# LAN.net
KiCad netlist of a schematic drawn in Altium Designer
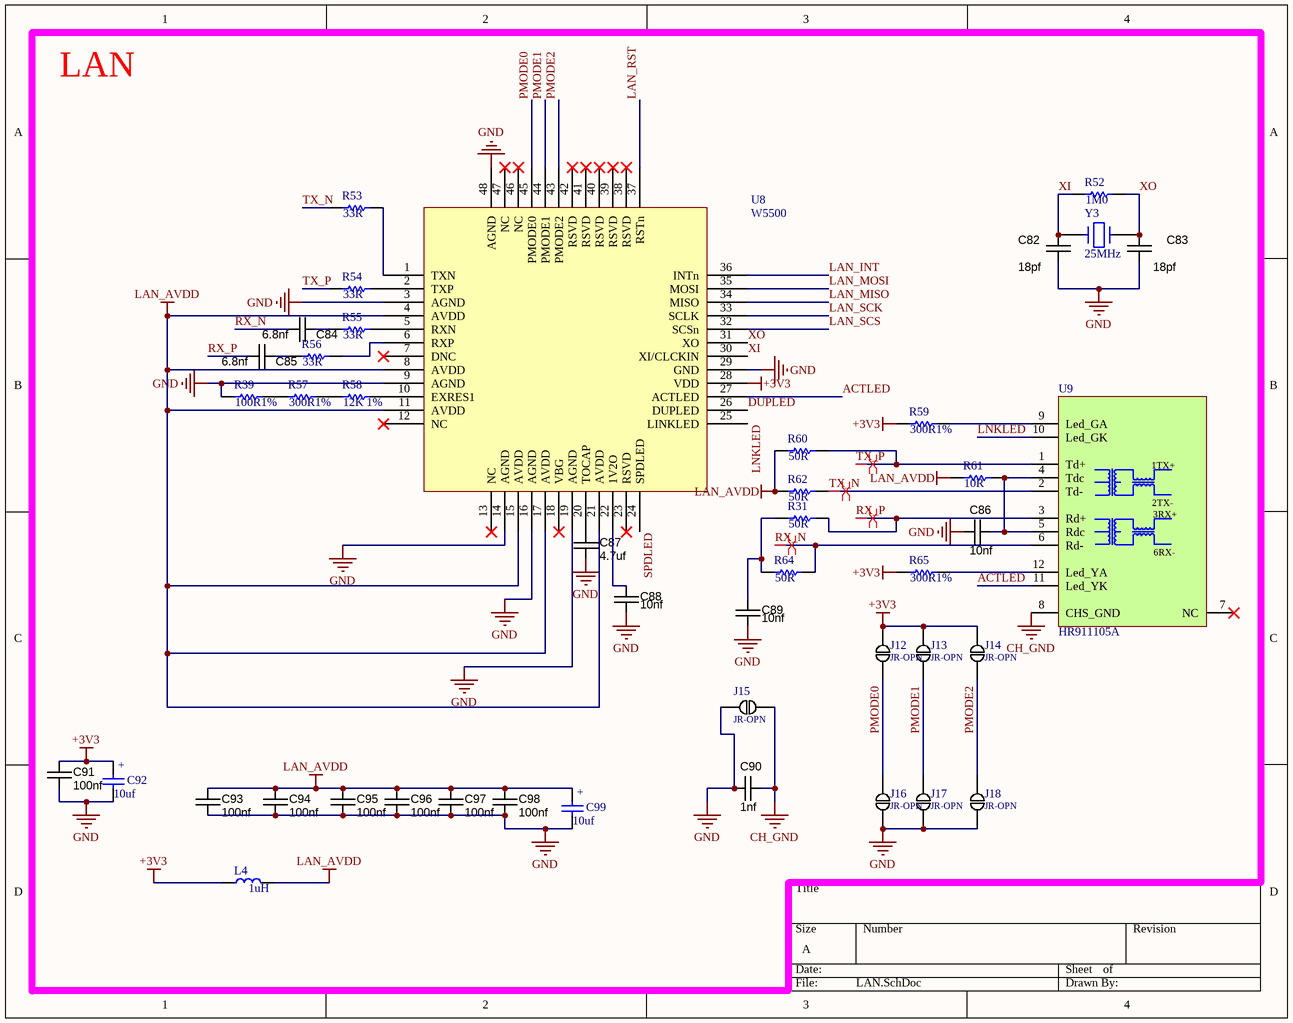
[diagram p0: LAN.SchDoc]

(export (version "E")
  (design (tool "Eeschema 10.0.6"))
  (components
    (comp (ref "C82")
      (value "18pf")
      (footprint "CAPC1608X90N")
      (description "Capacitor SMD Cer 100nF 10% 50V X7R 0603")
      (fields (field (name "TOLERANCE") "±10%"))
      (libsource (lib "altium-import") (part "root_2_CAPC_100n_0603_X7R_50V_10%_"))
    )
    (comp (ref "C83")
      (value "18pf")
      (footprint "CAPC1608X90N")
      (description "Capacitor SMD Cer 100nF 10% 50V X7R 0603")
      (fields (field (name "TOLERANCE") "±10%"))
      (libsource (lib "altium-import") (part "root_2_CAPC_100n_0603_X7R_50V_10%_"))
    )
    (comp (ref "C84")
      (value "6.8nf")
      (footprint "CAPC1608X90N")
      (description "Capacitor SMD Cer 100nF 10% 50V X7R 0603")
      (fields (field (name "TOLERANCE") "±10%"))
      (libsource (lib "altium-import") (part "root_3_CAPC_100n_0603_X7R_50V_10%_"))
    )
    (comp (ref "C85")
      (value "6.8nf")
      (footprint "CAPC1608X90N")
      (description "Capacitor SMD Cer 100nF 10% 50V X7R 0603")
      (fields (field (name "TOLERANCE") "±10%"))
      (libsource (lib "altium-import") (part "root_3_CAPC_100n_0603_X7R_50V_10%_"))
    )
    (comp (ref "C86")
      (value "10nf")
      (footprint "CAPC1608X90N")
      (description "Capacitor SMD Cer 100nF 10% 50V X7R 0603")
      (fields (field (name "TOLERANCE") "±10%"))
      (libsource (lib "altium-import") (part "root_1_CAPC_100n_0603_X7R_50V_10%_"))
    )
    (comp (ref "C87")
      (value "4.7uf")
      (footprint "CAPC1608X90N")
      (description "Capacitor SMD Cer 100nF 10% 50V X7R 0603")
      (fields (field (name "TOLERANCE") "±10%"))
      (libsource (lib "altium-import") (part "root_2_CAPC_100n_0603_X7R_50V_10%_"))
    )
    (comp (ref "C88")
      (value "10nf")
      (footprint "CAPC1608X90N")
      (description "Capacitor SMD Cer 100nF 10% 50V X7R 0603")
      (fields (field (name "TOLERANCE") "±10%"))
      (libsource (lib "altium-import") (part "root_2_CAPC_100n_0603_X7R_50V_10%_"))
    )
    (comp (ref "C89")
      (value "10nf")
      (footprint "CAPC1608X90N")
      (description "Capacitor SMD Cer 100nF 10% 50V X7R 0603")
      (fields (field (name "TOLERANCE") "±10%"))
      (libsource (lib "altium-import") (part "root_2_CAPC_100n_0603_X7R_50V_10%_"))
    )
    (comp (ref "C90")
      (value "1nf")
      (footprint "CAPC1608X90N")
      (description "Capacitor SMD Cer 100nF 10% 50V X7R 0603")
      (fields (field (name "TOLERANCE") "±10%"))
      (libsource (lib "altium-import") (part "root_1_CAPC_100n_0603_X7R_50V_10%_"))
    )
    (comp (ref "C91")
      (value "100nf")
      (footprint "CAPC1608X90N")
      (description "Capacitor SMD Cer 100nF 10% 50V X7R 0603")
      (fields (field (name "TOLERANCE") "±10%"))
      (libsource (lib "altium-import") (part "root_2_CAPC_100n_0603_X7R_50V_10%_"))
    )
    (comp (ref "C92")
      (value "10uf")
      (footprint "MY_CAP_SMD-A")
      (description "3.2X1.6MM")
      (libsource (lib "altium-import") (part "root_3_CAP_TANTAL_A_"))
    )
    (comp (ref "C93")
      (value "100nf")
      (footprint "CAPC1608X90N")
      (description "Capacitor SMD Cer 100nF 10% 50V X7R 0603")
      (fields (field (name "TOLERANCE") "±10%"))
      (libsource (lib "altium-import") (part "root_2_CAPC_100n_0603_X7R_50V_10%_"))
    )
    (comp (ref "C94")
      (value "100nf")
      (footprint "CAPC1608X90N")
      (description "Capacitor SMD Cer 100nF 10% 50V X7R 0603")
      (fields (field (name "TOLERANCE") "±10%"))
      (libsource (lib "altium-import") (part "root_2_CAPC_100n_0603_X7R_50V_10%_"))
    )
    (comp (ref "C95")
      (value "100nf")
      (footprint "CAPC1608X90N")
      (description "Capacitor SMD Cer 100nF 10% 50V X7R 0603")
      (fields (field (name "TOLERANCE") "±10%"))
      (libsource (lib "altium-import") (part "root_2_CAPC_100n_0603_X7R_50V_10%_"))
    )
    (comp (ref "C96")
      (value "100nf")
      (footprint "CAPC1608X90N")
      (description "Capacitor SMD Cer 100nF 10% 50V X7R 0603")
      (fields (field (name "TOLERANCE") "±10%"))
      (libsource (lib "altium-import") (part "root_2_CAPC_100n_0603_X7R_50V_10%_"))
    )
    (comp (ref "C97")
      (value "100nf")
      (footprint "CAPC1608X90N")
      (description "Capacitor SMD Cer 100nF 10% 50V X7R 0603")
      (fields (field (name "TOLERANCE") "±10%"))
      (libsource (lib "altium-import") (part "root_2_CAPC_100n_0603_X7R_50V_10%_"))
    )
    (comp (ref "C98")
      (value "100nf")
      (footprint "CAPC1608X90N")
      (description "Capacitor SMD Cer 100nF 10% 50V X7R 0603")
      (fields (field (name "TOLERANCE") "±10%"))
      (libsource (lib "altium-import") (part "root_2_CAPC_100n_0603_X7R_50V_10%_"))
    )
    (comp (ref "C99")
      (value "10uf")
      (footprint "MY_CAP_SMD-A")
      (description "3.2X1.6MM")
      (libsource (lib "altium-import") (part "root_3_CAP_TANTAL_A_"))
    )
    (comp (ref "J12")
      (value "JR-OPN")
      (footprint "0603-J")
      (description "SOLDERDOT BYPASS")
      (libsource (lib "*") (part "BYPASS"))
    )
    (comp (ref "J13")
      (value "JR-OPN")
      (footprint "0603-J")
      (description "SOLDERDOT BYPASS")
      (libsource (lib "*") (part "BYPASS"))
    )
    (comp (ref "J14")
      (value "JR-OPN")
      (footprint "0603-J")
      (description "SOLDERDOT BYPASS")
      (libsource (lib "*") (part "BYPASS"))
    )
    (comp (ref "J15")
      (value "JR-OPN")
      (footprint "0603-J")
      (description "SOLDERDOT BYPASS")
      (libsource (lib "*") (part "BYPASS"))
    )
    (comp (ref "J16")
      (value "JR-OPN")
      (footprint "0603-J")
      (description "SOLDERDOT BYPASS")
      (libsource (lib "*") (part "BYPASS"))
    )
    (comp (ref "J17")
      (value "JR-OPN")
      (footprint "0603-J")
      (description "SOLDERDOT BYPASS")
      (libsource (lib "*") (part "BYPASS"))
    )
    (comp (ref "J18")
      (value "JR-OPN")
      (footprint "0603-J")
      (description "SOLDERDOT BYPASS")
      (libsource (lib "*") (part "BYPASS"))
    )
    (comp (ref "L4")
      (value "1uH")
      (footprint "L0805")
      (description "Inductor SMD NC 0805")
      (libsource (lib "altium-import") (part "root_0_Inductor SMD NC 0805_"))
    )
    (comp (ref "R31")
      (value "50R")
      (footprint "Resistor_SMD_0603 (1608)")
      (description "Resistor 0603")
      (fields (field (name "PUBLISHER") "Seyed Razi Vesali") (field (name "EMAIL") "razi.vesali@gmail.com"))
      (libsource (lib "resistors") (part "Resistor"))
    )
    (comp (ref "R39")
      (value "100R1%")
      (footprint "Resistor_SMD_0603 (1608)")
      (description "Resistor 0603")
      (fields (field (name "PUBLISHER") "Seyed Razi Vesali") (field (name "EMAIL") "razi.vesali@gmail.com"))
      (libsource (lib "resistors") (part "Resistor"))
    )
    (comp (ref "R52")
      (value "1M0")
      (footprint "Resistor_SMD_0603 (1608)")
      (description "Resistor 0603")
      (fields (field (name "PUBLISHER") "Seyed Razi Vesali") (field (name "EMAIL") "razi.vesali@gmail.com"))
      (libsource (lib "resistors") (part "Resistor"))
    )
    (comp (ref "R53")
      (value "33R")
      (footprint "Resistor_SMD_0603 (1608)")
      (description "Resistor 0603")
      (fields (field (name "PUBLISHER") "Seyed Razi Vesali") (field (name "EMAIL") "razi.vesali@gmail.com"))
      (libsource (lib "resistors") (part "Resistor"))
    )
    (comp (ref "R54")
      (value "33R")
      (footprint "Resistor_SMD_0603 (1608)")
      (description "Resistor 0603")
      (fields (field (name "PUBLISHER") "Seyed Razi Vesali") (field (name "EMAIL") "razi.vesali@gmail.com"))
      (libsource (lib "resistors") (part "Resistor"))
    )
    (comp (ref "R55")
      (value "33R")
      (footprint "Resistor_SMD_0603 (1608)")
      (description "Resistor 0603")
      (fields (field (name "PUBLISHER") "Seyed Razi Vesali") (field (name "EMAIL") "razi.vesali@gmail.com"))
      (libsource (lib "resistors") (part "Resistor"))
    )
    (comp (ref "R56")
      (value "33R")
      (footprint "Resistor_SMD_0603 (1608)")
      (description "Resistor 0603")
      (fields (field (name "PUBLISHER") "Seyed Razi Vesali") (field (name "EMAIL") "razi.vesali@gmail.com"))
      (libsource (lib "resistors") (part "Resistor"))
    )
    (comp (ref "R57")
      (value "300R1%")
      (footprint "Resistor_SMD_0603 (1608)")
      (description "Resistor 0603")
      (fields (field (name "PUBLISHER") "Seyed Razi Vesali") (field (name "EMAIL") "razi.vesali@gmail.com"))
      (libsource (lib "resistors") (part "Resistor"))
    )
    (comp (ref "R58")
      (value "12K 1%")
      (footprint "Resistor_SMD_0603 (1608)")
      (description "Resistor 0603")
      (fields (field (name "PUBLISHER") "Seyed Razi Vesali") (field (name "EMAIL") "razi.vesali@gmail.com"))
      (libsource (lib "resistors") (part "Resistor"))
    )
    (comp (ref "R59")
      (value "300R1%")
      (footprint "Resistor_SMD_0603 (1608)")
      (description "Resistor 0603")
      (fields (field (name "PUBLISHER") "Seyed Razi Vesali") (field (name "EMAIL") "razi.vesali@gmail.com"))
      (libsource (lib "resistors") (part "Resistor"))
    )
    (comp (ref "R60")
      (value "50R")
      (footprint "Resistor_SMD_0603 (1608)")
      (description "Resistor 0603")
      (fields (field (name "PUBLISHER") "Seyed Razi Vesali") (field (name "EMAIL") "razi.vesali@gmail.com"))
      (libsource (lib "resistors") (part "Resistor"))
    )
    (comp (ref "R61")
      (value "10R")
      (footprint "Resistor_SMD_0603 (1608)")
      (description "Resistor 0603")
      (fields (field (name "PUBLISHER") "Seyed Razi Vesali") (field (name "EMAIL") "razi.vesali@gmail.com"))
      (libsource (lib "resistors") (part "Resistor"))
    )
    (comp (ref "R62")
      (value "50R")
      (footprint "Resistor_SMD_0603 (1608)")
      (description "Resistor 0603")
      (fields (field (name "PUBLISHER") "Seyed Razi Vesali") (field (name "EMAIL") "razi.vesali@gmail.com"))
      (libsource (lib "resistors") (part "Resistor"))
    )
    (comp (ref "R64")
      (value "50R")
      (footprint "Resistor_SMD_0603 (1608)")
      (description "Resistor 0603")
      (fields (field (name "PUBLISHER") "Seyed Razi Vesali") (field (name "EMAIL") "razi.vesali@gmail.com"))
      (libsource (lib "resistors") (part "Resistor"))
    )
    (comp (ref "R65")
      (value "300R1%")
      (footprint "Resistor_SMD_0603 (1608)")
      (description "Resistor 0603")
      (fields (field (name "PUBLISHER") "Seyed Razi Vesali") (field (name "EMAIL") "razi.vesali@gmail.com"))
      (libsource (lib "resistors") (part "Resistor"))
    )
    (comp (ref "U8")
      (value "W5500")
      (footprint "LQFP48")
      (description "Ethernet Controller, 10/100, SPI, DMA")
      (libsource (lib "altium-import") (part "root_0_W5500_"))
    )
    (comp (ref "U9")
      (value "HR911105A")
      (footprint "HR911105A")
      (description "RJ45, 10/100BASE, G/Y LED")
      (libsource (lib "altium-import") (part "root_0_HR911105A_"))
    )
    (comp (ref "Y3")
      (value "25MHz")
      (footprint "My_Crystal - SMD")
      (description "Crystal")
      (libsource (lib "altium-import") (part "root_0_CRYSTAL_SMD_"))
    )
  )
  (nets
    (net (code "1") (name "+3V3") (class "Default")
      (node (ref "C91") (pin "2") (pintype "passive"))
      (node (ref "C92") (pin "+") (pinfunction "+_+") (pintype "passive"))
      (node (ref "J12") (pin "1") (pinfunction "1_1") (pintype "passive"))
      (node (ref "J13") (pin "1") (pinfunction "1_1") (pintype "passive"))
      (node (ref "J14") (pin "1") (pinfunction "1_1") (pintype "passive"))
      (node (ref "L4") (pin "1") (pinfunction "1_1") (pintype "passive"))
      (node (ref "R59") (pin "1") (pinfunction "1_1") (pintype "passive"))
      (node (ref "R65") (pin "1") (pinfunction "1_1") (pintype "passive"))
      (node (ref "U8") (pin "28") (pinfunction "VDD_28") (pintype "passive"))
    )
    (net (code "2") (name "/ACTLED") (class "Default")
      (node (ref "U8") (pin "27") (pinfunction "ACTLED_27") (pintype "passive"))
      (node (ref "U9") (pin "11") (pinfunction "Led_YK_11") (pintype "passive"))
    )
    (net (code "3") (name "/DUPLED") (class "Default")
      (node (ref "U8") (pin "26") (pinfunction "DUPLED_26") (pintype "passive"))
    )
    (net (code "4") (name "/LAN_INT") (class "Default")
      (node (ref "U8") (pin "36") (pinfunction "INTn_36") (pintype "passive"))
    )
    (net (code "5") (name "/LAN_MISO") (class "Default")
      (node (ref "U8") (pin "34") (pinfunction "MISO_34") (pintype "passive"))
    )
    (net (code "6") (name "/LAN_MOSI") (class "Default")
      (node (ref "U8") (pin "35") (pinfunction "MOSI_35") (pintype "passive"))
    )
    (net (code "7") (name "/LAN_RST") (class "Default")
      (node (ref "U8") (pin "37") (pinfunction "RSTn_37") (pintype "passive"))
    )
    (net (code "8") (name "/LAN_SCK") (class "Default")
      (node (ref "U8") (pin "33") (pinfunction "SCLK_33") (pintype "passive"))
    )
    (net (code "9") (name "/LAN_SCS") (class "Default")
      (node (ref "U8") (pin "32") (pinfunction "SCSn_32") (pintype "passive"))
    )
    (net (code "10") (name "/LNKLED") (class "Default")
      (node (ref "U8") (pin "25") (pinfunction "LINKLED_25") (pintype "passive"))
      (node (ref "U9") (pin "10") (pinfunction "Led_GK_10") (pintype "passive"))
    )
    (net (code "11") (name "/PMODE0") (class "Default")
      (node (ref "J12") (pin "2") (pinfunction "2_2") (pintype "passive"))
      (node (ref "J16") (pin "1") (pinfunction "1_1") (pintype "passive"))
      (node (ref "U8") (pin "45") (pinfunction "PMODE0_45") (pintype "passive"))
    )
    (net (code "12") (name "/PMODE1") (class "Default")
      (node (ref "J13") (pin "2") (pinfunction "2_2") (pintype "passive"))
      (node (ref "J17") (pin "1") (pinfunction "1_1") (pintype "passive"))
      (node (ref "U8") (pin "44") (pinfunction "PMODE1_44") (pintype "passive"))
    )
    (net (code "13") (name "/PMODE2") (class "Default")
      (node (ref "J14") (pin "2") (pinfunction "2_2") (pintype "passive"))
      (node (ref "J18") (pin "1") (pinfunction "1_1") (pintype "passive"))
      (node (ref "U8") (pin "43") (pinfunction "PMODE2_43") (pintype "passive"))
    )
    (net (code "14") (name "/RX_N") (class "Default")
      (node (ref "C84") (pin "2") (pintype "passive"))
      (node (ref "R64") (pin "2") (pinfunction "2_2") (pintype "passive"))
      (node (ref "U9") (pin "6") (pinfunction "Rd-_6") (pintype "passive"))
    )
    (net (code "15") (name "/RX_P") (class "Default")
      (node (ref "C85") (pin "2") (pintype "passive"))
      (node (ref "R31") (pin "2") (pinfunction "2_2") (pintype "passive"))
      (node (ref "U9") (pin "3") (pinfunction "Rd+_3") (pintype "passive"))
    )
    (net (code "16") (name "/SPDLED") (class "Default")
      (node (ref "U8") (pin "24") (pinfunction "SPDLED_24") (pintype "passive"))
    )
    (net (code "17") (name "/TX_N") (class "Default")
      (node (ref "R53") (pin "1") (pinfunction "1_1") (pintype "passive"))
      (node (ref "R62") (pin "2") (pinfunction "2_2") (pintype "passive"))
      (node (ref "U9") (pin "2") (pinfunction "Td-_2") (pintype "passive"))
    )
    (net (code "18") (name "/TX_P") (class "Default")
      (node (ref "R54") (pin "1") (pinfunction "1_1") (pintype "passive"))
      (node (ref "R60") (pin "2") (pinfunction "2_2") (pintype "passive"))
      (node (ref "U9") (pin "1") (pinfunction "Td+_1") (pintype "passive"))
    )
    (net (code "19") (name "/XI") (class "Default")
      (node (ref "C82") (pin "2") (pintype "passive"))
      (node (ref "R52") (pin "1") (pinfunction "1_1") (pintype "passive"))
      (node (ref "U8") (pin "30") (pinfunction "XI/CLCKIN_30") (pintype "passive"))
      (node (ref "Y3") (pin "1") (pinfunction "1_1") (pintype "passive"))
    )
    (net (code "20") (name "/XO") (class "Default")
      (node (ref "C83") (pin "2") (pintype "passive"))
      (node (ref "R52") (pin "2") (pinfunction "2_2") (pintype "passive"))
      (node (ref "U8") (pin "31") (pinfunction "XO_31") (pintype "passive"))
      (node (ref "Y3") (pin "2") (pinfunction "2_2") (pintype "passive"))
    )
    (net (code "21") (name "CH_GND") (class "Default")
      (node (ref "C90") (pin "2") (pintype "passive"))
      (node (ref "J15") (pin "1") (pinfunction "1_1") (pintype "passive"))
      (node (ref "U9") (pin "8") (pinfunction "CHS_GND_8") (pintype "passive"))
    )
    (net (code "22") (name "GND") (class "Default")
      (node (ref "C82") (pin "1") (pintype "passive"))
      (node (ref "C83") (pin "1") (pintype "passive"))
      (node (ref "C86") (pin "1") (pintype "passive"))
      (node (ref "C87") (pin "1") (pintype "passive"))
      (node (ref "C88") (pin "1") (pintype "passive"))
      (node (ref "C89") (pin "1") (pintype "passive"))
      (node (ref "C90") (pin "1") (pintype "passive"))
      (node (ref "C91") (pin "1") (pintype "passive"))
      (node (ref "C92") (pin "-") (pinfunction "-_-") (pintype "passive"))
      (node (ref "C93") (pin "1") (pintype "passive"))
      (node (ref "C94") (pin "1") (pintype "passive"))
      (node (ref "C95") (pin "1") (pintype "passive"))
      (node (ref "C96") (pin "1") (pintype "passive"))
      (node (ref "C97") (pin "1") (pintype "passive"))
      (node (ref "C98") (pin "1") (pintype "passive"))
      (node (ref "C99") (pin "-") (pinfunction "-_-") (pintype "passive"))
      (node (ref "J15") (pin "2") (pinfunction "2_2") (pintype "passive"))
      (node (ref "J16") (pin "2") (pinfunction "2_2") (pintype "passive"))
      (node (ref "J17") (pin "2") (pinfunction "2_2") (pintype "passive"))
      (node (ref "J18") (pin "2") (pinfunction "2_2") (pintype "passive"))
      (node (ref "R39") (pin "1") (pinfunction "1_1") (pintype "passive"))
      (node (ref "U8") (pin "14") (pinfunction "AGND_14") (pintype "passive"))
      (node (ref "U8") (pin "16") (pinfunction "AGND_16") (pintype "passive"))
      (node (ref "U8") (pin "19") (pinfunction "AGND_19") (pintype "passive"))
      (node (ref "U8") (pin "29") (pinfunction "GND_29") (pintype "passive"))
      (node (ref "U8") (pin "3") (pinfunction "AGND_3") (pintype "passive"))
      (node (ref "U8") (pin "48") (pinfunction "AGND_48") (pintype "passive"))
      (node (ref "U8") (pin "9") (pinfunction "AGND_9") (pintype "passive"))
    )
    (net (code "23") (name "LAN_AVDD") (class "Default")
      (node (ref "C93") (pin "2") (pintype "passive"))
      (node (ref "C94") (pin "2") (pintype "passive"))
      (node (ref "C95") (pin "2") (pintype "passive"))
      (node (ref "C96") (pin "2") (pintype "passive"))
      (node (ref "C97") (pin "2") (pintype "passive"))
      (node (ref "C98") (pin "2") (pintype "passive"))
      (node (ref "C99") (pin "+") (pinfunction "+_+") (pintype "passive"))
      (node (ref "L4") (pin "2") (pinfunction "2_2") (pintype "passive"))
      (node (ref "R60") (pin "1") (pinfunction "1_1") (pintype "passive"))
      (node (ref "R61") (pin "1") (pinfunction "1_1") (pintype "passive"))
      (node (ref "R62") (pin "1") (pinfunction "1_1") (pintype "passive"))
      (node (ref "U8") (pin "11") (pinfunction "AVDD_11") (pintype "passive"))
      (node (ref "U8") (pin "15") (pinfunction "AVDD_15") (pintype "passive"))
      (node (ref "U8") (pin "17") (pinfunction "AVDD_17") (pintype "passive"))
      (node (ref "U8") (pin "21") (pinfunction "AVDD_21") (pintype "passive"))
      (node (ref "U8") (pin "4") (pinfunction "AVDD_4") (pintype "passive"))
      (node (ref "U8") (pin "8") (pinfunction "AVDD_8") (pintype "passive"))
    )
    (net (code "24") (name "Net-(C84-Pad1)") (class "Default")
      (node (ref "C84") (pin "1") (pintype "passive"))
      (node (ref "R55") (pin "1") (pinfunction "1_1") (pintype "passive"))
    )
    (net (code "25") (name "Net-(C85-Pad1)") (class "Default")
      (node (ref "C85") (pin "1") (pintype "passive"))
      (node (ref "R56") (pin "1") (pinfunction "1_1") (pintype "passive"))
    )
    (net (code "26") (name "Net-(C89-Pad2)") (class "Default")
      (node (ref "C89") (pin "2") (pintype "passive"))
      (node (ref "R31") (pin "1") (pinfunction "1_1") (pintype "passive"))
      (node (ref "R64") (pin "1") (pinfunction "1_1") (pintype "passive"))
    )
    (net (code "27") (name "Net-(R39-Pad2)") (class "Default")
      (node (ref "R39") (pin "2") (pinfunction "2_2") (pintype "passive"))
      (node (ref "R57") (pin "1") (pinfunction "1_1") (pintype "passive"))
    )
    (net (code "28") (name "Net-(R57-Pad2)") (class "Default")
      (node (ref "R57") (pin "2") (pinfunction "2_2") (pintype "passive"))
      (node (ref "R58") (pin "1") (pinfunction "1_1") (pintype "passive"))
    )
    (net (code "29") (name "Net-(U8-1V2O)") (class "Default")
      (node (ref "C88") (pin "2") (pintype "passive"))
      (node (ref "U8") (pin "22") (pinfunction "1V2O_22") (pintype "passive"))
    )
    (net (code "30") (name "Net-(U8-EXRES1)") (class "Default")
      (node (ref "R58") (pin "2") (pinfunction "2_2") (pintype "passive"))
      (node (ref "U8") (pin "10") (pinfunction "EXRES1_10") (pintype "passive"))
    )
    (net (code "31") (name "Net-(U8-RXN)") (class "Default")
      (node (ref "R55") (pin "2") (pinfunction "2_2") (pintype "passive"))
      (node (ref "U8") (pin "5") (pinfunction "RXN_5") (pintype "passive"))
    )
    (net (code "32") (name "Net-(U8-RXP)") (class "Default")
      (node (ref "R56") (pin "2") (pinfunction "2_2") (pintype "passive"))
      (node (ref "U8") (pin "6") (pinfunction "RXP_6") (pintype "passive"))
    )
    (net (code "33") (name "Net-(U8-TOCAP)") (class "Default")
      (node (ref "C87") (pin "2") (pintype "passive"))
      (node (ref "U8") (pin "20") (pinfunction "TOCAP_20") (pintype "passive"))
    )
    (net (code "34") (name "Net-(U8-TXN)") (class "Default")
      (node (ref "R53") (pin "2") (pinfunction "2_2") (pintype "passive"))
      (node (ref "U8") (pin "1") (pinfunction "TXN_1") (pintype "passive"))
    )
    (net (code "35") (name "Net-(U8-TXP)") (class "Default")
      (node (ref "R54") (pin "2") (pinfunction "2_2") (pintype "passive"))
      (node (ref "U8") (pin "2") (pinfunction "TXP_2") (pintype "passive"))
    )
    (net (code "36") (name "Net-(U9-Led_GA)") (class "Default")
      (node (ref "R59") (pin "2") (pinfunction "2_2") (pintype "passive"))
      (node (ref "U9") (pin "9") (pinfunction "Led_GA_9") (pintype "passive"))
    )
    (net (code "37") (name "Net-(U9-Led_YA)") (class "Default")
      (node (ref "R65") (pin "2") (pinfunction "2_2") (pintype "passive"))
      (node (ref "U9") (pin "12") (pinfunction "Led_YA_12") (pintype "passive"))
    )
    (net (code "38") (name "Net-(U9-Rdc)") (class "Default")
      (node (ref "C86") (pin "2") (pintype "passive"))
      (node (ref "R61") (pin "2") (pinfunction "2_2") (pintype "passive"))
      (node (ref "U9") (pin "4") (pinfunction "Tdc_4") (pintype "passive"))
      (node (ref "U9") (pin "5") (pinfunction "Rdc_5") (pintype "passive"))
    )
    (net (code "39") (name "unconnected-(U8-DNC-Pad7)") (class "Default")
      (node (ref "U8") (pin "7") (pinfunction "DNC_7") (pintype "passive+no_connect"))
    )
    (net (code "40") (name "unconnected-(U8-NC-Pad12)") (class "Default")
      (node (ref "U8") (pin "12") (pinfunction "NC_12") (pintype "passive+no_connect"))
    )
    (net (code "41") (name "unconnected-(U8-NC-Pad13)") (class "Default")
      (node (ref "U8") (pin "13") (pinfunction "NC_13") (pintype "passive+no_connect"))
    )
    (net (code "42") (name "unconnected-(U8-NC-Pad46)") (class "Default")
      (node (ref "U8") (pin "46") (pinfunction "NC_46") (pintype "passive+no_connect"))
    )
    (net (code "43") (name "unconnected-(U8-NC-Pad47)") (class "Default")
      (node (ref "U8") (pin "47") (pinfunction "NC_47") (pintype "passive+no_connect"))
    )
    (net (code "44") (name "unconnected-(U8-RSVD-Pad23)") (class "Default")
      (node (ref "U8") (pin "23") (pinfunction "RSVD_23") (pintype "passive+no_connect"))
    )
    (net (code "45") (name "unconnected-(U8-RSVD-Pad38)") (class "Default")
      (node (ref "U8") (pin "38") (pinfunction "RSVD_38") (pintype "passive+no_connect"))
    )
    (net (code "46") (name "unconnected-(U8-RSVD-Pad39)") (class "Default")
      (node (ref "U8") (pin "39") (pinfunction "RSVD_39") (pintype "passive+no_connect"))
    )
    (net (code "47") (name "unconnected-(U8-RSVD-Pad40)") (class "Default")
      (node (ref "U8") (pin "40") (pinfunction "RSVD_40") (pintype "passive+no_connect"))
    )
    (net (code "48") (name "unconnected-(U8-RSVD-Pad41)") (class "Default")
      (node (ref "U8") (pin "41") (pinfunction "RSVD_41") (pintype "passive+no_connect"))
    )
    (net (code "49") (name "unconnected-(U8-RSVD-Pad42)") (class "Default")
      (node (ref "U8") (pin "42") (pinfunction "RSVD_42") (pintype "passive+no_connect"))
    )
    (net (code "50") (name "unconnected-(U8-VBG-Pad18)") (class "Default")
      (node (ref "U8") (pin "18") (pinfunction "VBG_18") (pintype "passive+no_connect"))
    )
    (net (code "51") (name "unconnected-(U9-NC-Pad7)") (class "Default")
      (node (ref "U9") (pin "7") (pinfunction "NC_7") (pintype "passive+no_connect"))
    )
  )
)
